# SkinProc_v0_1b_sensors.net
KiCad netlist of a schematic drawn in EAGLE
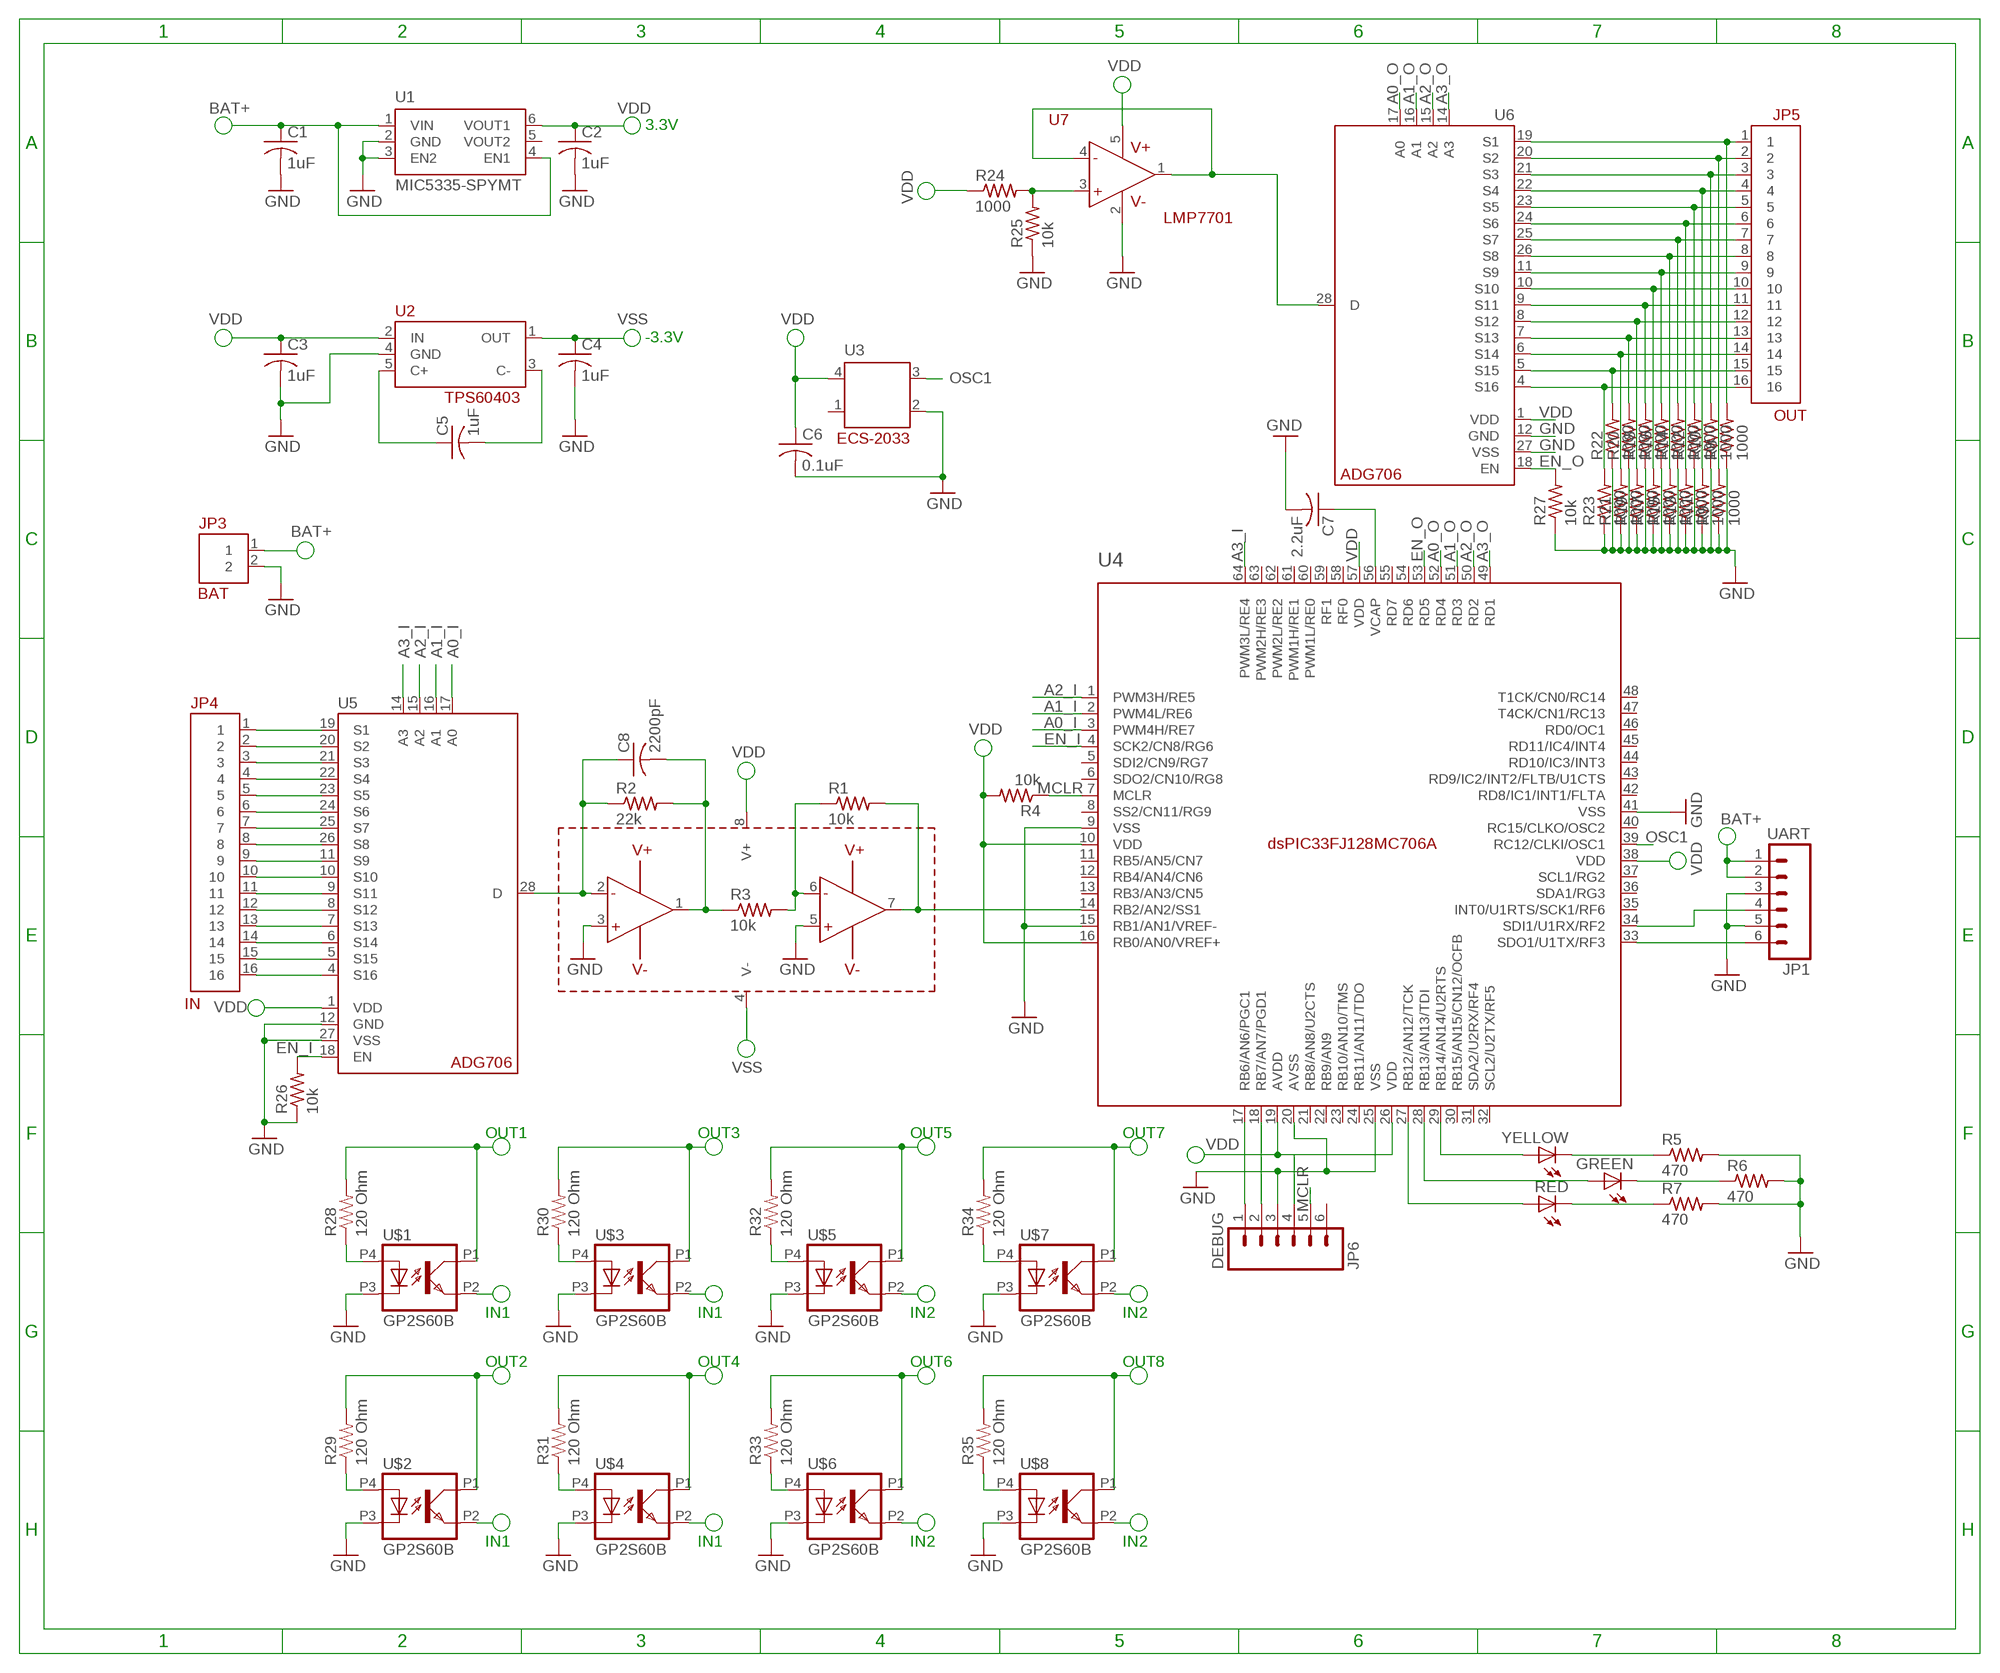
[diagram p0: schematic, sheet 1]

(export (version "E")
  (design (tool "Eeschema 10.0.6"))
  (components
    (comp (ref "C1")
      (value "1uF")
      (footprint "eagle-import:C0402")
      (libsource (lib "eagle-import") (part "C-USC0402"))
    )
    (comp (ref "C2")
      (value "1uF")
      (footprint "eagle-import:C0402")
      (libsource (lib "eagle-import") (part "C-USC0402"))
    )
    (comp (ref "C3")
      (value "1uF")
      (footprint "eagle-import:C0402")
      (libsource (lib "eagle-import") (part "C-USC0402"))
    )
    (comp (ref "C4")
      (value "1uF")
      (footprint "eagle-import:C0402")
      (libsource (lib "eagle-import") (part "C-USC0402"))
    )
    (comp (ref "C5")
      (value "1uF")
      (footprint "eagle-import:C0402")
      (libsource (lib "eagle-import") (part "C-USC0402"))
    )
    (comp (ref "C6")
      (value "0.1uF")
      (footprint "eagle-import:C0402")
      (libsource (lib "eagle-import") (part "C-USC0402"))
    )
    (comp (ref "C7")
      (value "2.2uF")
      (footprint "eagle-import:C0402")
      (libsource (lib "eagle-import") (part "C-USC0402"))
    )
    (comp (ref "C8")
      (value "2200pF")
      (footprint "eagle-import:C0402")
      (libsource (lib "eagle-import") (part "C-USC0402"))
    )
    (comp (ref "GREEN")
      (value "LEDCHIP-LED0603")
      (footprint "eagle-import:CHIP-LED0603")
      (libsource (lib "eagle-import") (part "LEDCHIP-LED0603"))
    )
    (comp (ref "JP1")
      (value "UART")
      (footprint "eagle-import:MOLEX_503480-0600")
      (libsource (lib "eagle-import") (part "MOLEX_503480-0600"))
    )
    (comp (ref "JP3")
      (value "BAT")
      (footprint "eagle-import:2_PAD")
      (libsource (lib "eagle-import") (part "2_PAD"))
    )
    (comp (ref "JP4")
      (value "IN")
      (footprint "eagle-import:16_PAD")
      (libsource (lib "eagle-import") (part "16_PAD"))
    )
    (comp (ref "JP5")
      (value "OUT")
      (footprint "eagle-import:16_PAD")
      (libsource (lib "eagle-import") (part "16_PAD"))
    )
    (comp (ref "JP6")
      (value "DEBUG")
      (footprint "eagle-import:MOLEX_503480-0600")
      (libsource (lib "eagle-import") (part "MOLEX_503480-0600"))
    )
    (comp (ref "R1")
      (value "10k")
      (footprint "eagle-import:R0402")
      (libsource (lib "eagle-import") (part "R-US_R0402"))
    )
    (comp (ref "R2")
      (value "22k")
      (footprint "eagle-import:R0402")
      (libsource (lib "eagle-import") (part "R-US_R0402"))
    )
    (comp (ref "R3")
      (value "10k")
      (footprint "eagle-import:R0402")
      (libsource (lib "eagle-import") (part "R-US_R0402"))
    )
    (comp (ref "R4")
      (value "10k")
      (footprint "eagle-import:R0402")
      (libsource (lib "eagle-import") (part "R-US_R0402"))
    )
    (comp (ref "R5")
      (value "470")
      (footprint "eagle-import:R0402")
      (libsource (lib "eagle-import") (part "R-US_R0402"))
    )
    (comp (ref "R6")
      (value "470")
      (footprint "eagle-import:R0402")
      (libsource (lib "eagle-import") (part "R-US_R0402"))
    )
    (comp (ref "R7")
      (value "470")
      (footprint "eagle-import:R0402")
      (libsource (lib "eagle-import") (part "R-US_R0402"))
    )
    (comp (ref "R8")
      (value "1000")
      (footprint "eagle-import:R0402")
      (libsource (lib "eagle-import") (part "R-US_R0402"))
    )
    (comp (ref "R9")
      (value "1000")
      (footprint "eagle-import:R0402")
      (libsource (lib "eagle-import") (part "R-US_R0402"))
    )
    (comp (ref "R10")
      (value "1000")
      (footprint "eagle-import:R0402")
      (libsource (lib "eagle-import") (part "R-US_R0402"))
    )
    (comp (ref "R11")
      (value "1000")
      (footprint "eagle-import:R0402")
      (libsource (lib "eagle-import") (part "R-US_R0402"))
    )
    (comp (ref "R12")
      (value "1000")
      (footprint "eagle-import:R0402")
      (libsource (lib "eagle-import") (part "R-US_R0402"))
    )
    (comp (ref "R13")
      (value "1000")
      (footprint "eagle-import:R0402")
      (libsource (lib "eagle-import") (part "R-US_R0402"))
    )
    (comp (ref "R14")
      (value "1000")
      (footprint "eagle-import:R0402")
      (libsource (lib "eagle-import") (part "R-US_R0402"))
    )
    (comp (ref "R15")
      (value "1000")
      (footprint "eagle-import:R0402")
      (libsource (lib "eagle-import") (part "R-US_R0402"))
    )
    (comp (ref "R16")
      (value "1000")
      (footprint "eagle-import:R0402")
      (libsource (lib "eagle-import") (part "R-US_R0402"))
    )
    (comp (ref "R17")
      (value "1000")
      (footprint "eagle-import:R0402")
      (libsource (lib "eagle-import") (part "R-US_R0402"))
    )
    (comp (ref "R18")
      (value "1000")
      (footprint "eagle-import:R0402")
      (libsource (lib "eagle-import") (part "R-US_R0402"))
    )
    (comp (ref "R19")
      (value "1000")
      (footprint "eagle-import:R0402")
      (libsource (lib "eagle-import") (part "R-US_R0402"))
    )
    (comp (ref "R20")
      (value "1000")
      (footprint "eagle-import:R0402")
      (libsource (lib "eagle-import") (part "R-US_R0402"))
    )
    (comp (ref "R21")
      (value "1000")
      (footprint "eagle-import:R0402")
      (libsource (lib "eagle-import") (part "R-US_R0402"))
    )
    (comp (ref "R22")
      (value "1000")
      (footprint "eagle-import:R0402")
      (libsource (lib "eagle-import") (part "R-US_R0402"))
    )
    (comp (ref "R23")
      (value "1000")
      (footprint "eagle-import:R0402")
      (libsource (lib "eagle-import") (part "R-US_R0402"))
    )
    (comp (ref "R24")
      (value "1000")
      (footprint "eagle-import:R0402")
      (libsource (lib "eagle-import") (part "R-US_R0402"))
    )
    (comp (ref "R25")
      (value "10k")
      (footprint "eagle-import:R0402")
      (libsource (lib "eagle-import") (part "R-US_R0402"))
    )
    (comp (ref "R26")
      (value "10k")
      (footprint "eagle-import:R0402")
      (libsource (lib "eagle-import") (part "R-US_R0402"))
    )
    (comp (ref "R27")
      (value "10k")
      (footprint "eagle-import:R0402")
      (libsource (lib "eagle-import") (part "R-US_R0402"))
    )
    (comp (ref "R28")
      (value "120 Ohm")
      (footprint "eagle-import:0402-RES")
      (libsource (lib "eagle-import") (part "RESISTOR0402-RES"))
    )
    (comp (ref "R29")
      (value "120 Ohm")
      (footprint "eagle-import:0402-RES")
      (libsource (lib "eagle-import") (part "RESISTOR0402-RES"))
    )
    (comp (ref "R30")
      (value "120 Ohm")
      (footprint "eagle-import:0402-RES")
      (libsource (lib "eagle-import") (part "RESISTOR0402-RES"))
    )
    (comp (ref "R31")
      (value "120 Ohm")
      (footprint "eagle-import:0402-RES")
      (libsource (lib "eagle-import") (part "RESISTOR0402-RES"))
    )
    (comp (ref "R32")
      (value "120 Ohm")
      (footprint "eagle-import:0402-RES")
      (libsource (lib "eagle-import") (part "RESISTOR0402-RES"))
    )
    (comp (ref "R33")
      (value "120 Ohm")
      (footprint "eagle-import:0402-RES")
      (libsource (lib "eagle-import") (part "RESISTOR0402-RES"))
    )
    (comp (ref "R34")
      (value "120 Ohm")
      (footprint "eagle-import:0402-RES")
      (libsource (lib "eagle-import") (part "RESISTOR0402-RES"))
    )
    (comp (ref "R35")
      (value "120 Ohm")
      (footprint "eagle-import:0402-RES")
      (libsource (lib "eagle-import") (part "RESISTOR0402-RES"))
    )
    (comp (ref "RED")
      (value "LEDCHIP-LED0603")
      (footprint "eagle-import:CHIP-LED0603")
      (libsource (lib "eagle-import") (part "LEDCHIP-LED0603"))
    )
    (comp (ref "U$1")
      (value "GP2S60B")
      (footprint "eagle-import:4-SMD")
      (libsource (lib "eagle-import") (part "GP2S60B"))
    )
    (comp (ref "U$2")
      (value "GP2S60B")
      (footprint "eagle-import:4-SMD")
      (libsource (lib "eagle-import") (part "GP2S60B"))
    )
    (comp (ref "U$3")
      (value "GP2S60B")
      (footprint "eagle-import:4-SMD")
      (libsource (lib "eagle-import") (part "GP2S60B"))
    )
    (comp (ref "U$4")
      (value "GP2S60B")
      (footprint "eagle-import:4-SMD")
      (libsource (lib "eagle-import") (part "GP2S60B"))
    )
    (comp (ref "U$5")
      (value "GP2S60B")
      (footprint "eagle-import:4-SMD")
      (libsource (lib "eagle-import") (part "GP2S60B"))
    )
    (comp (ref "U$6")
      (value "GP2S60B")
      (footprint "eagle-import:4-SMD")
      (libsource (lib "eagle-import") (part "GP2S60B"))
    )
    (comp (ref "U$7")
      (value "GP2S60B")
      (footprint "eagle-import:4-SMD")
      (libsource (lib "eagle-import") (part "GP2S60B"))
    )
    (comp (ref "U$8")
      (value "GP2S60B")
      (footprint "eagle-import:4-SMD")
      (libsource (lib "eagle-import") (part "GP2S60B"))
    )
    (comp (ref "U1")
      (value "MIC5335-SPYMT")
      (footprint "eagle-import:MLF-6")
      (libsource (lib "eagle-import") (part "MIC5320-JGYML"))
    )
    (comp (ref "U2")
      (value "TPS60403")
      (footprint "eagle-import:SOT23-DBV")
      (libsource (lib "eagle-import") (part "TPS60403"))
    )
    (comp (ref "U3")
      (value "OSCILLATORS")
      (footprint "eagle-import:OSCILLATOR-SMD")
      (libsource (lib "eagle-import") (part "OSCILLATORS"))
    )
    (comp (ref "U4")
      (value "DSPIC33FJ128MC706-I/PT")
      (footprint "eagle-import:TQFP64")
      (libsource (lib "eagle-import") (part "DSPIC33FJ128MC706-I/PT"))
    )
    (comp (ref "U5")
      (value "ADG706")
      (footprint "eagle-import:TSSOP28")
      (libsource (lib "eagle-import") (part "ADG706"))
    )
    (comp (ref "U6")
      (value "ADG706")
      (footprint "eagle-import:TSSOP28")
      (libsource (lib "eagle-import") (part "ADG706"))
    )
    (comp (ref "U7")
      (value "LMP7701")
      (footprint "eagle-import:SOT23-DBV")
      (libsource (lib "eagle-import") (part "NATIONAL_OP_AMP_SINGLE"))
    )
    (comp (ref "U8")
      (value "NATIONAL_OP_AMP")
      (footprint "eagle-import:SO08")
      (libsource (lib "eagle-import") (part "NATIONAL_OP_AMP"))
    )
    (comp (ref "YELLOW")
      (value "LEDCHIP-LED0603")
      (footprint "eagle-import:CHIP-LED0603")
      (libsource (lib "eagle-import") (part "LEDCHIP-LED0603"))
    )
  )
  (nets
    (net (code "1") (name "/A0_I") (class "Default")
      (node (ref "U4") (pin "3") (pinfunction "PWM4H/RE7_3") (pintype "bidirectional"))
      (node (ref "U5") (pin "17") (pinfunction "A0_17") (pintype "bidirectional"))
    )
    (net (code "2") (name "/A0_O") (class "Default")
      (node (ref "U4") (pin "52") (pinfunction "RD4_52") (pintype "bidirectional"))
      (node (ref "U6") (pin "17") (pinfunction "A0_17") (pintype "bidirectional"))
    )
    (net (code "3") (name "/A1_I") (class "Default")
      (node (ref "U4") (pin "2") (pinfunction "PWM4L/RE6_2") (pintype "bidirectional"))
      (node (ref "U5") (pin "16") (pinfunction "A1_16") (pintype "bidirectional"))
    )
    (net (code "4") (name "/A1_O") (class "Default")
      (node (ref "U4") (pin "51") (pinfunction "RD3_51") (pintype "bidirectional"))
      (node (ref "U6") (pin "16") (pinfunction "A1_16") (pintype "bidirectional"))
    )
    (net (code "5") (name "/A2_I") (class "Default")
      (node (ref "U4") (pin "1") (pinfunction "PWM3H/RE5_1") (pintype "bidirectional"))
      (node (ref "U5") (pin "15") (pinfunction "A2_15") (pintype "bidirectional"))
    )
    (net (code "6") (name "/A2_O") (class "Default")
      (node (ref "U4") (pin "50") (pinfunction "RD2_50") (pintype "bidirectional"))
      (node (ref "U6") (pin "15") (pinfunction "A2_15") (pintype "bidirectional"))
    )
    (net (code "7") (name "/A3_I") (class "Default")
      (node (ref "U4") (pin "64") (pinfunction "PWM3L/RE4_64") (pintype "bidirectional"))
      (node (ref "U5") (pin "14") (pinfunction "A3_14") (pintype "bidirectional"))
    )
    (net (code "8") (name "/A3_O") (class "Default")
      (node (ref "U4") (pin "49") (pinfunction "RD1_49") (pintype "bidirectional"))
      (node (ref "U6") (pin "14") (pinfunction "A3_14") (pintype "bidirectional"))
    )
    (net (code "9") (name "/BAT+") (class "Default")
      (node (ref "C1") (pin "1") (pinfunction "1_1") (pintype "passive"))
      (node (ref "JP1") (pin "1") (pinfunction "1_1") (pintype "passive"))
      (node (ref "JP1") (pin "2") (pinfunction "2_2") (pintype "passive"))
      (node (ref "JP3") (pin "1") (pinfunction "1_1") (pintype "bidirectional"))
      (node (ref "U1") (pin "1") (pinfunction "VIN_1") (pintype "bidirectional"))
      (node (ref "U1") (pin "4") (pinfunction "EN1_4") (pintype "bidirectional"))
    )
    (net (code "10") (name "/EN_I") (class "Default")
      (node (ref "R26") (pin "2") (pinfunction "2_2") (pintype "passive"))
      (node (ref "U4") (pin "4") (pinfunction "SCK2/CN8/RG6_4") (pintype "bidirectional"))
      (node (ref "U5") (pin "18") (pinfunction "EN_18") (pintype "bidirectional"))
    )
    (net (code "11") (name "/EN_O") (class "Default")
      (node (ref "R27") (pin "2") (pinfunction "2_2") (pintype "passive"))
      (node (ref "U4") (pin "53") (pinfunction "RD5_53") (pintype "bidirectional"))
      (node (ref "U6") (pin "18") (pinfunction "EN_18") (pintype "bidirectional"))
    )
    (net (code "12") (name "/IN1") (class "Default")
      (node (ref "JP4") (pin "1") (pinfunction "1_1") (pintype "bidirectional"))
      (node (ref "U$1") (pin "P2") (pinfunction "2_P2") (pintype "passive"))
      (node (ref "U$2") (pin "P2") (pinfunction "2_P2") (pintype "passive"))
      (node (ref "U$3") (pin "P2") (pinfunction "2_P2") (pintype "passive"))
      (node (ref "U$4") (pin "P2") (pinfunction "2_P2") (pintype "passive"))
      (node (ref "U5") (pin "19") (pinfunction "S1_19") (pintype "bidirectional"))
    )
    (net (code "13") (name "/IN2") (class "Default")
      (node (ref "JP4") (pin "2") (pinfunction "2_2") (pintype "bidirectional"))
      (node (ref "U$5") (pin "P2") (pinfunction "2_P2") (pintype "passive"))
      (node (ref "U$6") (pin "P2") (pinfunction "2_P2") (pintype "passive"))
      (node (ref "U$7") (pin "P2") (pinfunction "2_P2") (pintype "passive"))
      (node (ref "U$8") (pin "P2") (pinfunction "2_P2") (pintype "passive"))
      (node (ref "U5") (pin "20") (pinfunction "S2_20") (pintype "bidirectional"))
    )
    (net (code "14") (name "/MCLR") (class "Default")
      (node (ref "JP6") (pin "5") (pinfunction "5_5") (pintype "passive"))
      (node (ref "R4") (pin "1") (pinfunction "1_1") (pintype "passive"))
      (node (ref "U4") (pin "7") (pinfunction "MCLR_7") (pintype "input"))
    )
    (net (code "15") (name "/OSC1") (class "Default")
      (node (ref "U3") (pin "3") (pinfunction "OUT_3") (pintype "bidirectional"))
      (node (ref "U4") (pin "39") (pinfunction "RC12/CLKI/OSC1_39") (pintype "bidirectional"))
    )
    (net (code "16") (name "/OUT1") (class "Default")
      (node (ref "JP5") (pin "1") (pinfunction "1_1") (pintype "bidirectional"))
      (node (ref "R28") (pin "2") (pinfunction "2_2") (pintype "passive"))
      (node (ref "R8") (pin "2") (pinfunction "2_2") (pintype "passive"))
      (node (ref "U$1") (pin "P1") (pinfunction "1_P1") (pintype "passive"))
      (node (ref "U6") (pin "19") (pinfunction "S1_19") (pintype "bidirectional"))
    )
    (net (code "17") (name "/OUT2") (class "Default")
      (node (ref "JP5") (pin "2") (pinfunction "2_2") (pintype "bidirectional"))
      (node (ref "R29") (pin "2") (pinfunction "2_2") (pintype "passive"))
      (node (ref "R9") (pin "2") (pinfunction "2_2") (pintype "passive"))
      (node (ref "U$2") (pin "P1") (pinfunction "1_P1") (pintype "passive"))
      (node (ref "U6") (pin "20") (pinfunction "S2_20") (pintype "bidirectional"))
    )
    (net (code "18") (name "/OUT3") (class "Default")
      (node (ref "JP5") (pin "3") (pinfunction "3_3") (pintype "bidirectional"))
      (node (ref "R10") (pin "2") (pinfunction "2_2") (pintype "passive"))
      (node (ref "R30") (pin "2") (pinfunction "2_2") (pintype "passive"))
      (node (ref "U$3") (pin "P1") (pinfunction "1_P1") (pintype "passive"))
      (node (ref "U6") (pin "21") (pinfunction "S3_21") (pintype "bidirectional"))
    )
    (net (code "19") (name "/OUT4") (class "Default")
      (node (ref "JP5") (pin "4") (pinfunction "4_4") (pintype "bidirectional"))
      (node (ref "R11") (pin "2") (pinfunction "2_2") (pintype "passive"))
      (node (ref "R31") (pin "2") (pinfunction "2_2") (pintype "passive"))
      (node (ref "U$4") (pin "P1") (pinfunction "1_P1") (pintype "passive"))
      (node (ref "U6") (pin "22") (pinfunction "S4_22") (pintype "bidirectional"))
    )
    (net (code "20") (name "/OUT5") (class "Default")
      (node (ref "JP5") (pin "5") (pinfunction "5_5") (pintype "bidirectional"))
      (node (ref "R12") (pin "2") (pinfunction "2_2") (pintype "passive"))
      (node (ref "R32") (pin "2") (pinfunction "2_2") (pintype "passive"))
      (node (ref "U$5") (pin "P1") (pinfunction "1_P1") (pintype "passive"))
      (node (ref "U6") (pin "23") (pinfunction "S5_23") (pintype "bidirectional"))
    )
    (net (code "21") (name "/OUT6") (class "Default")
      (node (ref "JP5") (pin "6") (pinfunction "6_6") (pintype "bidirectional"))
      (node (ref "R13") (pin "2") (pinfunction "2_2") (pintype "passive"))
      (node (ref "R33") (pin "2") (pinfunction "2_2") (pintype "passive"))
      (node (ref "U$6") (pin "P1") (pinfunction "1_P1") (pintype "passive"))
      (node (ref "U6") (pin "24") (pinfunction "S6_24") (pintype "bidirectional"))
    )
    (net (code "22") (name "/OUT7") (class "Default")
      (node (ref "JP5") (pin "7") (pinfunction "7_7") (pintype "bidirectional"))
      (node (ref "R14") (pin "2") (pinfunction "2_2") (pintype "passive"))
      (node (ref "R34") (pin "2") (pinfunction "2_2") (pintype "passive"))
      (node (ref "U$7") (pin "P1") (pinfunction "1_P1") (pintype "passive"))
      (node (ref "U6") (pin "25") (pinfunction "S7_25") (pintype "bidirectional"))
    )
    (net (code "23") (name "/OUT8") (class "Default")
      (node (ref "JP5") (pin "8") (pinfunction "8_8") (pintype "bidirectional"))
      (node (ref "R15") (pin "2") (pinfunction "2_2") (pintype "passive"))
      (node (ref "R35") (pin "2") (pinfunction "2_2") (pintype "passive"))
      (node (ref "U$8") (pin "P1") (pinfunction "1_P1") (pintype "passive"))
      (node (ref "U6") (pin "26") (pinfunction "S8_26") (pintype "bidirectional"))
    )
    (net (code "24") (name "/VDD") (class "Default")
      (node (ref "C2") (pin "1") (pinfunction "1_1") (pintype "passive"))
      (node (ref "C3") (pin "1") (pinfunction "1_1") (pintype "passive"))
      (node (ref "C6") (pin "1") (pinfunction "1_1") (pintype "passive"))
      (node (ref "JP6") (pin "4") (pinfunction "4_4") (pintype "passive"))
      (node (ref "R24") (pin "1") (pinfunction "1_1") (pintype "passive"))
      (node (ref "R4") (pin "2") (pinfunction "2_2") (pintype "passive"))
      (node (ref "U1") (pin "6") (pinfunction "VOUT1_6") (pintype "bidirectional"))
      (node (ref "U2") (pin "2") (pinfunction "IN_2") (pintype "bidirectional"))
      (node (ref "U3") (pin "4") (pinfunction "VDD_4") (pintype "bidirectional"))
      (node (ref "U4") (pin "10") (pinfunction "VDD_10") (pintype "power_in"))
      (node (ref "U4") (pin "16") (pinfunction "RB0/AN0/VREF+_16") (pintype "bidirectional"))
      (node (ref "U4") (pin "19") (pinfunction "AVDD_19") (pintype "power_in"))
      (node (ref "U4") (pin "26") (pinfunction "VDD_26") (pintype "power_in"))
      (node (ref "U4") (pin "38") (pinfunction "VDD_38") (pintype "power_in"))
      (node (ref "U4") (pin "57") (pinfunction "VDD_57") (pintype "power_in"))
      (node (ref "U5") (pin "1") (pinfunction "VDD_1") (pintype "bidirectional"))
      (node (ref "U6") (pin "1") (pinfunction "VDD_1") (pintype "bidirectional"))
      (node (ref "U7") (pin "5") (pinfunction "V+_5") (pintype "bidirectional"))
      (node (ref "U8") (pin "8") (pinfunction "V+_8") (pintype "bidirectional"))
    )
    (net (code "25") (name "/VSS") (class "Default")
      (node (ref "C4") (pin "1") (pinfunction "1_1") (pintype "passive"))
      (node (ref "U2") (pin "1") (pinfunction "OUT_1") (pintype "bidirectional"))
      (node (ref "U8") (pin "4") (pinfunction "V-_4") (pintype "bidirectional"))
    )
    (net (code "26") (name "GND") (class "Default")
      (node (ref "C1") (pin "2") (pinfunction "2_2") (pintype "passive"))
      (node (ref "C2") (pin "2") (pinfunction "2_2") (pintype "passive"))
      (node (ref "C3") (pin "2") (pinfunction "2_2") (pintype "passive"))
      (node (ref "C4") (pin "2") (pinfunction "2_2") (pintype "passive"))
      (node (ref "C6") (pin "2") (pinfunction "2_2") (pintype "passive"))
      (node (ref "C7") (pin "2") (pinfunction "2_2") (pintype "passive"))
      (node (ref "JP1") (pin "3") (pinfunction "3_3") (pintype "passive"))
      (node (ref "JP1") (pin "5") (pinfunction "5_5") (pintype "passive"))
      (node (ref "JP3") (pin "2") (pinfunction "2_2") (pintype "bidirectional"))
      (node (ref "JP6") (pin "3") (pinfunction "3_3") (pintype "passive"))
      (node (ref "R10") (pin "1") (pinfunction "1_1") (pintype "passive"))
      (node (ref "R11") (pin "1") (pinfunction "1_1") (pintype "passive"))
      (node (ref "R12") (pin "1") (pinfunction "1_1") (pintype "passive"))
      (node (ref "R13") (pin "1") (pinfunction "1_1") (pintype "passive"))
      (node (ref "R14") (pin "1") (pinfunction "1_1") (pintype "passive"))
      (node (ref "R15") (pin "1") (pinfunction "1_1") (pintype "passive"))
      (node (ref "R16") (pin "1") (pinfunction "1_1") (pintype "passive"))
      (node (ref "R17") (pin "1") (pinfunction "1_1") (pintype "passive"))
      (node (ref "R18") (pin "1") (pinfunction "1_1") (pintype "passive"))
      (node (ref "R19") (pin "1") (pinfunction "1_1") (pintype "passive"))
      (node (ref "R20") (pin "1") (pinfunction "1_1") (pintype "passive"))
      (node (ref "R21") (pin "1") (pinfunction "1_1") (pintype "passive"))
      (node (ref "R22") (pin "1") (pinfunction "1_1") (pintype "passive"))
      (node (ref "R23") (pin "1") (pinfunction "1_1") (pintype "passive"))
      (node (ref "R25") (pin "1") (pinfunction "1_1") (pintype "passive"))
      (node (ref "R26") (pin "1") (pinfunction "1_1") (pintype "passive"))
      (node (ref "R27") (pin "1") (pinfunction "1_1") (pintype "passive"))
      (node (ref "R5") (pin "2") (pinfunction "2_2") (pintype "passive"))
      (node (ref "R6") (pin "2") (pinfunction "2_2") (pintype "passive"))
      (node (ref "R7") (pin "2") (pinfunction "2_2") (pintype "passive"))
      (node (ref "R8") (pin "1") (pinfunction "1_1") (pintype "passive"))
      (node (ref "R9") (pin "1") (pinfunction "1_1") (pintype "passive"))
      (node (ref "U$1") (pin "P3") (pinfunction "3_P3") (pintype "passive"))
      (node (ref "U$2") (pin "P3") (pinfunction "3_P3") (pintype "passive"))
      (node (ref "U$3") (pin "P3") (pinfunction "3_P3") (pintype "passive"))
      (node (ref "U$4") (pin "P3") (pinfunction "3_P3") (pintype "passive"))
      (node (ref "U$5") (pin "P3") (pinfunction "3_P3") (pintype "passive"))
      (node (ref "U$6") (pin "P3") (pinfunction "3_P3") (pintype "passive"))
      (node (ref "U$7") (pin "P3") (pinfunction "3_P3") (pintype "passive"))
      (node (ref "U$8") (pin "P3") (pinfunction "3_P3") (pintype "passive"))
      (node (ref "U1") (pin "2") (pinfunction "GND_2") (pintype "bidirectional"))
      (node (ref "U1") (pin "3") (pinfunction "EN2_3") (pintype "bidirectional"))
      (node (ref "U2") (pin "4") (pinfunction "GND_4") (pintype "bidirectional"))
      (node (ref "U3") (pin "2") (pinfunction "GND_2") (pintype "bidirectional"))
      (node (ref "U4") (pin "15") (pinfunction "RB1/AN1/VREF-_15") (pintype "bidirectional"))
      (node (ref "U4") (pin "20") (pinfunction "AVSS_20") (pintype "power_in"))
      (node (ref "U4") (pin "25") (pinfunction "VSS_25") (pintype "power_in"))
      (node (ref "U4") (pin "41") (pinfunction "VSS_41") (pintype "power_in"))
      (node (ref "U4") (pin "9") (pinfunction "VSS_9") (pintype "power_in"))
      (node (ref "U5") (pin "12") (pinfunction "GND_12") (pintype "bidirectional"))
      (node (ref "U5") (pin "27") (pinfunction "VSS_27") (pintype "bidirectional"))
      (node (ref "U6") (pin "12") (pinfunction "GND_12") (pintype "bidirectional"))
      (node (ref "U6") (pin "27") (pinfunction "VSS_27") (pintype "bidirectional"))
      (node (ref "U7") (pin "2") (pinfunction "V-_2") (pintype "bidirectional"))
      (node (ref "U8") (pin "3") (pinfunction "+A_3") (pintype "bidirectional"))
      (node (ref "U8") (pin "5") (pinfunction "+B_5") (pintype "bidirectional"))
    )
    (net (code "27") (name "Net-(GREEN-PadC)") (class "Default")
      (node (ref "GREEN") (pin "C") (pinfunction "C_C") (pintype "passive"))
      (node (ref "R6") (pin "1") (pinfunction "1_1") (pintype "passive"))
    )
    (net (code "28") (name "Net-(R5-Pad1)") (class "Default")
      (node (ref "R5") (pin "1") (pinfunction "1_1") (pintype "passive"))
      (node (ref "YELLOW") (pin "C") (pinfunction "C_C") (pintype "passive"))
    )
    (net (code "29") (name "Net-(R7-Pad1)") (class "Default")
      (node (ref "R7") (pin "1") (pinfunction "1_1") (pintype "passive"))
      (node (ref "RED") (pin "C") (pinfunction "C_C") (pintype "passive"))
    )
    (net (code "30") (name "Net-(U$1-4)") (class "Default")
      (node (ref "R28") (pin "1") (pinfunction "1_1") (pintype "passive"))
      (node (ref "U$1") (pin "P4") (pinfunction "4_P4") (pintype "passive"))
    )
    (net (code "31") (name "Net-(U$2-4)") (class "Default")
      (node (ref "R29") (pin "1") (pinfunction "1_1") (pintype "passive"))
      (node (ref "U$2") (pin "P4") (pinfunction "4_P4") (pintype "passive"))
    )
    (net (code "32") (name "Net-(U$3-4)") (class "Default")
      (node (ref "R30") (pin "1") (pinfunction "1_1") (pintype "passive"))
      (node (ref "U$3") (pin "P4") (pinfunction "4_P4") (pintype "passive"))
    )
    (net (code "33") (name "Net-(U$4-4)") (class "Default")
      (node (ref "R31") (pin "1") (pinfunction "1_1") (pintype "passive"))
      (node (ref "U$4") (pin "P4") (pinfunction "4_P4") (pintype "passive"))
    )
    (net (code "34") (name "Net-(U$5-4)") (class "Default")
      (node (ref "R32") (pin "1") (pinfunction "1_1") (pintype "passive"))
      (node (ref "U$5") (pin "P4") (pinfunction "4_P4") (pintype "passive"))
    )
    (net (code "35") (name "Net-(U$6-4)") (class "Default")
      (node (ref "R33") (pin "1") (pinfunction "1_1") (pintype "passive"))
      (node (ref "U$6") (pin "P4") (pinfunction "4_P4") (pintype "passive"))
    )
    (net (code "36") (name "Net-(U$7-4)") (class "Default")
      (node (ref "R34") (pin "1") (pinfunction "1_1") (pintype "passive"))
      (node (ref "U$7") (pin "P4") (pinfunction "4_P4") (pintype "passive"))
    )
    (net (code "37") (name "Net-(U$8-4)") (class "Default")
      (node (ref "R35") (pin "1") (pinfunction "1_1") (pintype "passive"))
      (node (ref "U$8") (pin "P4") (pinfunction "4_P4") (pintype "passive"))
    )
    (net (code "38") (name "Net-(U2-C+)") (class "Default")
      (node (ref "C5") (pin "1") (pinfunction "1_1") (pintype "passive"))
      (node (ref "U2") (pin "5") (pinfunction "C+_5") (pintype "bidirectional"))
    )
    (net (code "39") (name "Net-(U2-C-)") (class "Default")
      (node (ref "C5") (pin "2") (pinfunction "2_2") (pintype "passive"))
      (node (ref "U2") (pin "3") (pinfunction "C-_3") (pintype "bidirectional"))
    )
    (net (code "40") (name "Net-(U4-RB2{slash}AN2{slash}SS1)") (class "Default")
      (node (ref "R1") (pin "2") (pinfunction "2_2") (pintype "passive"))
      (node (ref "U4") (pin "14") (pinfunction "RB2/AN2/SS1_14") (pintype "bidirectional"))
      (node (ref "U8") (pin "7") (pinfunction "VOUTB_7") (pintype "bidirectional"))
    )
    (net (code "41") (name "Net-(U4-RB6{slash}AN6{slash}PGC1)") (class "Default")
      (node (ref "JP6") (pin "1") (pinfunction "1_1") (pintype "passive"))
      (node (ref "U4") (pin "17") (pinfunction "RB6/AN6/PGC1_17") (pintype "bidirectional"))
    )
    (net (code "42") (name "Net-(U4-RB7{slash}AN7{slash}PGD1)") (class "Default")
      (node (ref "JP6") (pin "2") (pinfunction "2_2") (pintype "passive"))
      (node (ref "U4") (pin "18") (pinfunction "RB7/AN7/PGD1_18") (pintype "bidirectional"))
    )
    (net (code "43") (name "Net-(U4-RB12{slash}AN12{slash}TCK)") (class "Default")
      (node (ref "RED") (pin "A") (pinfunction "A_A") (pintype "passive"))
      (node (ref "U4") (pin "27") (pinfunction "RB12/AN12/TCK_27") (pintype "bidirectional"))
    )
    (net (code "44") (name "Net-(U4-RB13{slash}AN13{slash}TDI)") (class "Default")
      (node (ref "GREEN") (pin "A") (pinfunction "A_A") (pintype "passive"))
      (node (ref "U4") (pin "28") (pinfunction "RB13/AN13/TDI_28") (pintype "bidirectional"))
    )
    (net (code "45") (name "Net-(U4-RB14{slash}AN14{slash}U2RTS)") (class "Default")
      (node (ref "U4") (pin "29") (pinfunction "RB14/AN14/U2RTS_29") (pintype "bidirectional"))
      (node (ref "YELLOW") (pin "A") (pinfunction "A_A") (pintype "passive"))
    )
    (net (code "46") (name "Net-(U4-SDI1{slash}U1RX{slash}RF2)") (class "Default")
      (node (ref "JP1") (pin "4") (pinfunction "4_4") (pintype "passive"))
      (node (ref "U4") (pin "34") (pinfunction "SDI1/U1RX/RF2_34") (pintype "bidirectional"))
    )
    (net (code "47") (name "Net-(U4-SDO1{slash}U1TX{slash}RF3)") (class "Default")
      (node (ref "JP1") (pin "6") (pinfunction "6_6") (pintype "passive"))
      (node (ref "U4") (pin "33") (pinfunction "SDO1/U1TX/RF3_33") (pintype "bidirectional"))
    )
    (net (code "48") (name "Net-(U4-VCAP)") (class "Default")
      (node (ref "C7") (pin "1") (pinfunction "1_1") (pintype "passive"))
      (node (ref "U4") (pin "56") (pinfunction "VCAP_56") (pintype "power_in"))
    )
    (net (code "49") (name "Net-(U5-D)") (class "Default")
      (node (ref "C8") (pin "1") (pinfunction "1_1") (pintype "passive"))
      (node (ref "R2") (pin "1") (pinfunction "1_1") (pintype "passive"))
      (node (ref "U5") (pin "28") (pinfunction "D_28") (pintype "bidirectional"))
      (node (ref "U8") (pin "2") (pinfunction "-A_2") (pintype "bidirectional"))
    )
    (net (code "50") (name "Net-(U5-S3)") (class "Default")
      (node (ref "JP4") (pin "3") (pinfunction "3_3") (pintype "bidirectional"))
      (node (ref "U5") (pin "21") (pinfunction "S3_21") (pintype "bidirectional"))
    )
    (net (code "51") (name "Net-(U5-S4)") (class "Default")
      (node (ref "JP4") (pin "4") (pinfunction "4_4") (pintype "bidirectional"))
      (node (ref "U5") (pin "22") (pinfunction "S4_22") (pintype "bidirectional"))
    )
    (net (code "52") (name "Net-(U5-S5)") (class "Default")
      (node (ref "JP4") (pin "5") (pinfunction "5_5") (pintype "bidirectional"))
      (node (ref "U5") (pin "23") (pinfunction "S5_23") (pintype "bidirectional"))
    )
    (net (code "53") (name "Net-(U5-S6)") (class "Default")
      (node (ref "JP4") (pin "6") (pinfunction "6_6") (pintype "bidirectional"))
      (node (ref "U5") (pin "24") (pinfunction "S6_24") (pintype "bidirectional"))
    )
    (net (code "54") (name "Net-(U5-S7)") (class "Default")
      (node (ref "JP4") (pin "7") (pinfunction "7_7") (pintype "bidirectional"))
      (node (ref "U5") (pin "25") (pinfunction "S7_25") (pintype "bidirectional"))
    )
    (net (code "55") (name "Net-(U5-S8)") (class "Default")
      (node (ref "JP4") (pin "8") (pinfunction "8_8") (pintype "bidirectional"))
      (node (ref "U5") (pin "26") (pinfunction "S8_26") (pintype "bidirectional"))
    )
    (net (code "56") (name "Net-(U5-S9)") (class "Default")
      (node (ref "JP4") (pin "9") (pinfunction "9_9") (pintype "bidirectional"))
      (node (ref "U5") (pin "11") (pinfunction "S9_11") (pintype "bidirectional"))
    )
    (net (code "57") (name "Net-(U5-S10)") (class "Default")
      (node (ref "JP4") (pin "10") (pinfunction "10_10") (pintype "bidirectional"))
      (node (ref "U5") (pin "10") (pinfunction "S10_10") (pintype "bidirectional"))
    )
    (net (code "58") (name "Net-(U5-S11)") (class "Default")
      (node (ref "JP4") (pin "11") (pinfunction "11_11") (pintype "bidirectional"))
      (node (ref "U5") (pin "9") (pinfunction "S11_9") (pintype "bidirectional"))
    )
    (net (code "59") (name "Net-(U5-S12)") (class "Default")
      (node (ref "JP4") (pin "12") (pinfunction "12_12") (pintype "bidirectional"))
      (node (ref "U5") (pin "8") (pinfunction "S12_8") (pintype "bidirectional"))
    )
    (net (code "60") (name "Net-(U5-S13)") (class "Default")
      (node (ref "JP4") (pin "13") (pinfunction "13_13") (pintype "bidirectional"))
      (node (ref "U5") (pin "7") (pinfunction "S13_7") (pintype "bidirectional"))
    )
    (net (code "61") (name "Net-(U5-S14)") (class "Default")
      (node (ref "JP4") (pin "14") (pinfunction "14_14") (pintype "bidirectional"))
      (node (ref "U5") (pin "6") (pinfunction "S14_6") (pintype "bidirectional"))
    )
    (net (code "62") (name "Net-(U5-S15)") (class "Default")
      (node (ref "JP4") (pin "15") (pinfunction "15_15") (pintype "bidirectional"))
      (node (ref "U5") (pin "5") (pinfunction "S15_5") (pintype "bidirectional"))
    )
    (net (code "63") (name "Net-(U5-S16)") (class "Default")
      (node (ref "JP4") (pin "16") (pinfunction "16_16") (pintype "bidirectional"))
      (node (ref "U5") (pin "4") (pinfunction "S16_4") (pintype "bidirectional"))
    )
    (net (code "64") (name "Net-(U6-D)") (class "Default")
      (node (ref "U6") (pin "28") (pinfunction "D_28") (pintype "bidirectional"))
      (node (ref "U7") (pin "1") (pinfunction "VOUT_1") (pintype "bidirectional"))
      (node (ref "U7") (pin "4") (pinfunction "-_4") (pintype "bidirectional"))
    )
    (net (code "65") (name "Net-(U6-S9)") (class "Default")
      (node (ref "JP5") (pin "9") (pinfunction "9_9") (pintype "bidirectional"))
      (node (ref "R16") (pin "2") (pinfunction "2_2") (pintype "passive"))
      (node (ref "U6") (pin "11") (pinfunction "S9_11") (pintype "bidirectional"))
    )
    (net (code "66") (name "Net-(U6-S10)") (class "Default")
      (node (ref "JP5") (pin "10") (pinfunction "10_10") (pintype "bidirectional"))
      (node (ref "R17") (pin "2") (pinfunction "2_2") (pintype "passive"))
      (node (ref "U6") (pin "10") (pinfunction "S10_10") (pintype "bidirectional"))
    )
    (net (code "67") (name "Net-(U6-S11)") (class "Default")
      (node (ref "JP5") (pin "11") (pinfunction "11_11") (pintype "bidirectional"))
      (node (ref "R18") (pin "2") (pinfunction "2_2") (pintype "passive"))
      (node (ref "U6") (pin "9") (pinfunction "S11_9") (pintype "bidirectional"))
    )
    (net (code "68") (name "Net-(U6-S12)") (class "Default")
      (node (ref "JP5") (pin "12") (pinfunction "12_12") (pintype "bidirectional"))
      (node (ref "R19") (pin "2") (pinfunction "2_2") (pintype "passive"))
      (node (ref "U6") (pin "8") (pinfunction "S12_8") (pintype "bidirectional"))
    )
    (net (code "69") (name "Net-(U6-S13)") (class "Default")
      (node (ref "JP5") (pin "13") (pinfunction "13_13") (pintype "bidirectional"))
      (node (ref "R20") (pin "2") (pinfunction "2_2") (pintype "passive"))
      (node (ref "U6") (pin "7") (pinfunction "S13_7") (pintype "bidirectional"))
    )
    (net (code "70") (name "Net-(U6-S14)") (class "Default")
      (node (ref "JP5") (pin "14") (pinfunction "14_14") (pintype "bidirectional"))
      (node (ref "R21") (pin "2") (pinfunction "2_2") (pintype "passive"))
      (node (ref "U6") (pin "6") (pinfunction "S14_6") (pintype "bidirectional"))
    )
    (net (code "71") (name "Net-(U6-S15)") (class "Default")
      (node (ref "JP5") (pin "15") (pinfunction "15_15") (pintype "bidirectional"))
      (node (ref "R22") (pin "2") (pinfunction "2_2") (pintype "passive"))
      (node (ref "U6") (pin "5") (pinfunction "S15_5") (pintype "bidirectional"))
    )
    (net (code "72") (name "Net-(U6-S16)") (class "Default")
      (node (ref "JP5") (pin "16") (pinfunction "16_16") (pintype "bidirectional"))
      (node (ref "R23") (pin "2") (pinfunction "2_2") (pintype "passive"))
      (node (ref "U6") (pin "4") (pinfunction "S16_4") (pintype "bidirectional"))
    )
    (net (code "73") (name "Net-(U7-+)") (class "Default")
      (node (ref "R24") (pin "2") (pinfunction "2_2") (pintype "passive"))
      (node (ref "R25") (pin "2") (pinfunction "2_2") (pintype "passive"))
      (node (ref "U7") (pin "3") (pinfunction "+_3") (pintype "bidirectional"))
    )
    (net (code "74") (name "Net-(U8--B)") (class "Default")
      (node (ref "R1") (pin "1") (pinfunction "1_1") (pintype "passive"))
      (node (ref "R3") (pin "2") (pinfunction "2_2") (pintype "passive"))
      (node (ref "U8") (pin "6") (pinfunction "-B_6") (pintype "bidirectional"))
    )
    (net (code "75") (name "Net-(U8-VOUTA)") (class "Default")
      (node (ref "C8") (pin "2") (pinfunction "2_2") (pintype "passive"))
      (node (ref "R2") (pin "2") (pinfunction "2_2") (pintype "passive"))
      (node (ref "R3") (pin "1") (pinfunction "1_1") (pintype "passive"))
      (node (ref "U8") (pin "1") (pinfunction "VOUTA_1") (pintype "bidirectional"))
    )
    (net (code "76") (name "unconnected-(JP6-Pad6)") (class "Default")
      (node (ref "JP6") (pin "6") (pinfunction "6_6") (pintype "passive"))
    )
    (net (code "77") (name "unconnected-(U1-VOUT2-Pad5)") (class "Default")
      (node (ref "U1") (pin "5") (pinfunction "VOUT2_5") (pintype "bidirectional"))
    )
    (net (code "78") (name "unconnected-(U3-NC-Pad1)") (class "Default")
      (node (ref "U3") (pin "1") (pinfunction "NC_1") (pintype "bidirectional"))
    )
    (net (code "79") (name "unconnected-(U4-INT0{slash}U1RTS{slash}SCK1{slash}RF6-Pad35)") (class "Default")
      (node (ref "U4") (pin "35") (pinfunction "INT0/U1RTS/SCK1/RF6_35") (pintype "bidirectional"))
    )
    (net (code "80") (name "unconnected-(U4-PWM1H{slash}RE1-Pad61)") (class "Default")
      (node (ref "U4") (pin "61") (pinfunction "PWM1H/RE1_61") (pintype "bidirectional"))
    )
    (net (code "81") (name "unconnected-(U4-PWM1L{slash}RE0-Pad60)") (class "Default")
      (node (ref "U4") (pin "60") (pinfunction "PWM1L/RE0_60") (pintype "bidirectional"))
    )
    (net (code "82") (name "unconnected-(U4-PWM2H{slash}RE3-Pad63)") (class "Default")
      (node (ref "U4") (pin "63") (pinfunction "PWM2H/RE3_63") (pintype "bidirectional"))
    )
    (net (code "83") (name "unconnected-(U4-PWM2L{slash}RE2-Pad62)") (class "Default")
      (node (ref "U4") (pin "62") (pinfunction "PWM2L/RE2_62") (pintype "bidirectional"))
    )
    (net (code "84") (name "unconnected-(U4-RB3{slash}AN3{slash}CN5-Pad13)") (class "Default")
      (node (ref "U4") (pin "13") (pinfunction "RB3/AN3/CN5_13") (pintype "bidirectional"))
    )
    (net (code "85") (name "unconnected-(U4-RB4{slash}AN4{slash}CN6-Pad12)") (class "Default")
      (node (ref "U4") (pin "12") (pinfunction "RB4/AN4/CN6_12") (pintype "bidirectional"))
    )
    (net (code "86") (name "unconnected-(U4-RB5{slash}AN5{slash}CN7-Pad11)") (class "Default")
      (node (ref "U4") (pin "11") (pinfunction "RB5/AN5/CN7_11") (pintype "bidirectional"))
    )
    (net (code "87") (name "unconnected-(U4-RB8{slash}AN8{slash}U2CTS-Pad21)") (class "Default")
      (node (ref "U4") (pin "21") (pinfunction "RB8/AN8/U2CTS_21") (pintype "bidirectional"))
    )
    (net (code "88") (name "unconnected-(U4-RB9{slash}AN9-Pad22)") (class "Default")
      (node (ref "U4") (pin "22") (pinfunction "RB9/AN9_22") (pintype "bidirectional"))
    )
    (net (code "89") (name "unconnected-(U4-RB10{slash}AN10{slash}TMS-Pad23)") (class "Default")
      (node (ref "U4") (pin "23") (pinfunction "RB10/AN10/TMS_23") (pintype "bidirectional"))
    )
    (net (code "90") (name "unconnected-(U4-RB11{slash}AN11{slash}TDO-Pad24)") (class "Default")
      (node (ref "U4") (pin "24") (pinfunction "RB11/AN11/TDO_24") (pintype "bidirectional"))
    )
    (net (code "91") (name "unconnected-(U4-RB15{slash}AN15{slash}CN12{slash}OCFB-Pad30)") (class "Default")
      (node (ref "U4") (pin "30") (pinfunction "RB15/AN15/CN12/OCFB_30") (pintype "bidirectional"))
    )
    (net (code "92") (name "unconnected-(U4-RC15{slash}CLKO{slash}OSC2-Pad40)") (class "Default")
      (node (ref "U4") (pin "40") (pinfunction "RC15/CLKO/OSC2_40") (pintype "bidirectional"))
    )
    (net (code "93") (name "unconnected-(U4-RD0{slash}OC1-Pad46)") (class "Default")
      (node (ref "U4") (pin "46") (pinfunction "RD0/OC1_46") (pintype "bidirectional"))
    )
    (net (code "94") (name "unconnected-(U4-RD6-Pad54)") (class "Default")
      (node (ref "U4") (pin "54") (pinfunction "RD6_54") (pintype "bidirectional"))
    )
    (net (code "95") (name "unconnected-(U4-RD7-Pad55)") (class "Default")
      (node (ref "U4") (pin "55") (pinfunction "RD7_55") (pintype "bidirectional"))
    )
    (net (code "96") (name "unconnected-(U4-RD8{slash}IC1{slash}INT1{slash}FLTA-Pad42)") (class "Default")
      (node (ref "U4") (pin "42") (pinfunction "RD8/IC1/INT1/FLTA_42") (pintype "bidirectional"))
    )
    (net (code "97") (name "unconnected-(U4-RD9{slash}IC2{slash}INT2{slash}FLTB{slash}U1CTS-Pad43)") (class "Default")
      (node (ref "U4") (pin "43") (pinfunction "RD9/IC2/INT2/FLTB/U1CTS_43") (pintype "bidirectional"))
    )
    (net (code "98") (name "unconnected-(U4-RD10{slash}IC3{slash}INT3-Pad44)") (class "Default")
      (node (ref "U4") (pin "44") (pinfunction "RD10/IC3/INT3_44") (pintype "bidirectional"))
    )
    (net (code "99") (name "unconnected-(U4-RD11{slash}IC4{slash}INT4-Pad45)") (class "Default")
      (node (ref "U4") (pin "45") (pinfunction "RD11/IC4/INT4_45") (pintype "bidirectional"))
    )
    (net (code "100") (name "unconnected-(U4-RF0-Pad58)") (class "Default")
      (node (ref "U4") (pin "58") (pinfunction "RF0_58") (pintype "bidirectional"))
    )
    (net (code "101") (name "unconnected-(U4-RF1-Pad59)") (class "Default")
      (node (ref "U4") (pin "59") (pinfunction "RF1_59") (pintype "bidirectional"))
    )
    (net (code "102") (name "unconnected-(U4-SCL1{slash}RG2-Pad37)") (class "Default")
      (node (ref "U4") (pin "37") (pinfunction "SCL1/RG2_37") (pintype "bidirectional"))
    )
    (net (code "103") (name "unconnected-(U4-SCL2{slash}U2TX{slash}RF5-Pad32)") (class "Default")
      (node (ref "U4") (pin "32") (pinfunction "SCL2/U2TX/RF5_32") (pintype "bidirectional"))
    )
    (net (code "104") (name "unconnected-(U4-SDA1{slash}RG3-Pad36)") (class "Default")
      (node (ref "U4") (pin "36") (pinfunction "SDA1/RG3_36") (pintype "bidirectional"))
    )
    (net (code "105") (name "unconnected-(U4-SDA2{slash}U2RX{slash}RF4-Pad31)") (class "Default")
      (node (ref "U4") (pin "31") (pinfunction "SDA2/U2RX/RF4_31") (pintype "bidirectional"))
    )
    (net (code "106") (name "unconnected-(U4-SDI2{slash}CN9{slash}RG7-Pad5)") (class "Default")
      (node (ref "U4") (pin "5") (pinfunction "SDI2/CN9/RG7_5") (pintype "bidirectional"))
    )
    (net (code "107") (name "unconnected-(U4-SDO2{slash}CN10{slash}RG8-Pad6)") (class "Default")
      (node (ref "U4") (pin "6") (pinfunction "SDO2/CN10/RG8_6") (pintype "bidirectional"))
    )
    (net (code "108") (name "unconnected-(U4-SS2{slash}CN11{slash}RG9-Pad8)") (class "Default")
      (node (ref "U4") (pin "8") (pinfunction "SS2/CN11/RG9_8") (pintype "bidirectional"))
    )
    (net (code "109") (name "unconnected-(U4-T1CK{slash}CN0{slash}RC14-Pad48)") (class "Default")
      (node (ref "U4") (pin "48") (pinfunction "T1CK/CN0/RC14_48") (pintype "bidirectional"))
    )
    (net (code "110") (name "unconnected-(U4-T4CK{slash}CN1{slash}RC13-Pad47)") (class "Default")
      (node (ref "U4") (pin "47") (pinfunction "T4CK/CN1/RC13_47") (pintype "bidirectional"))
    )
  )
)
